# ATmega328P_Xplained_Mini_Target.net
KiCad netlist of a schematic drawn in Altium Designer
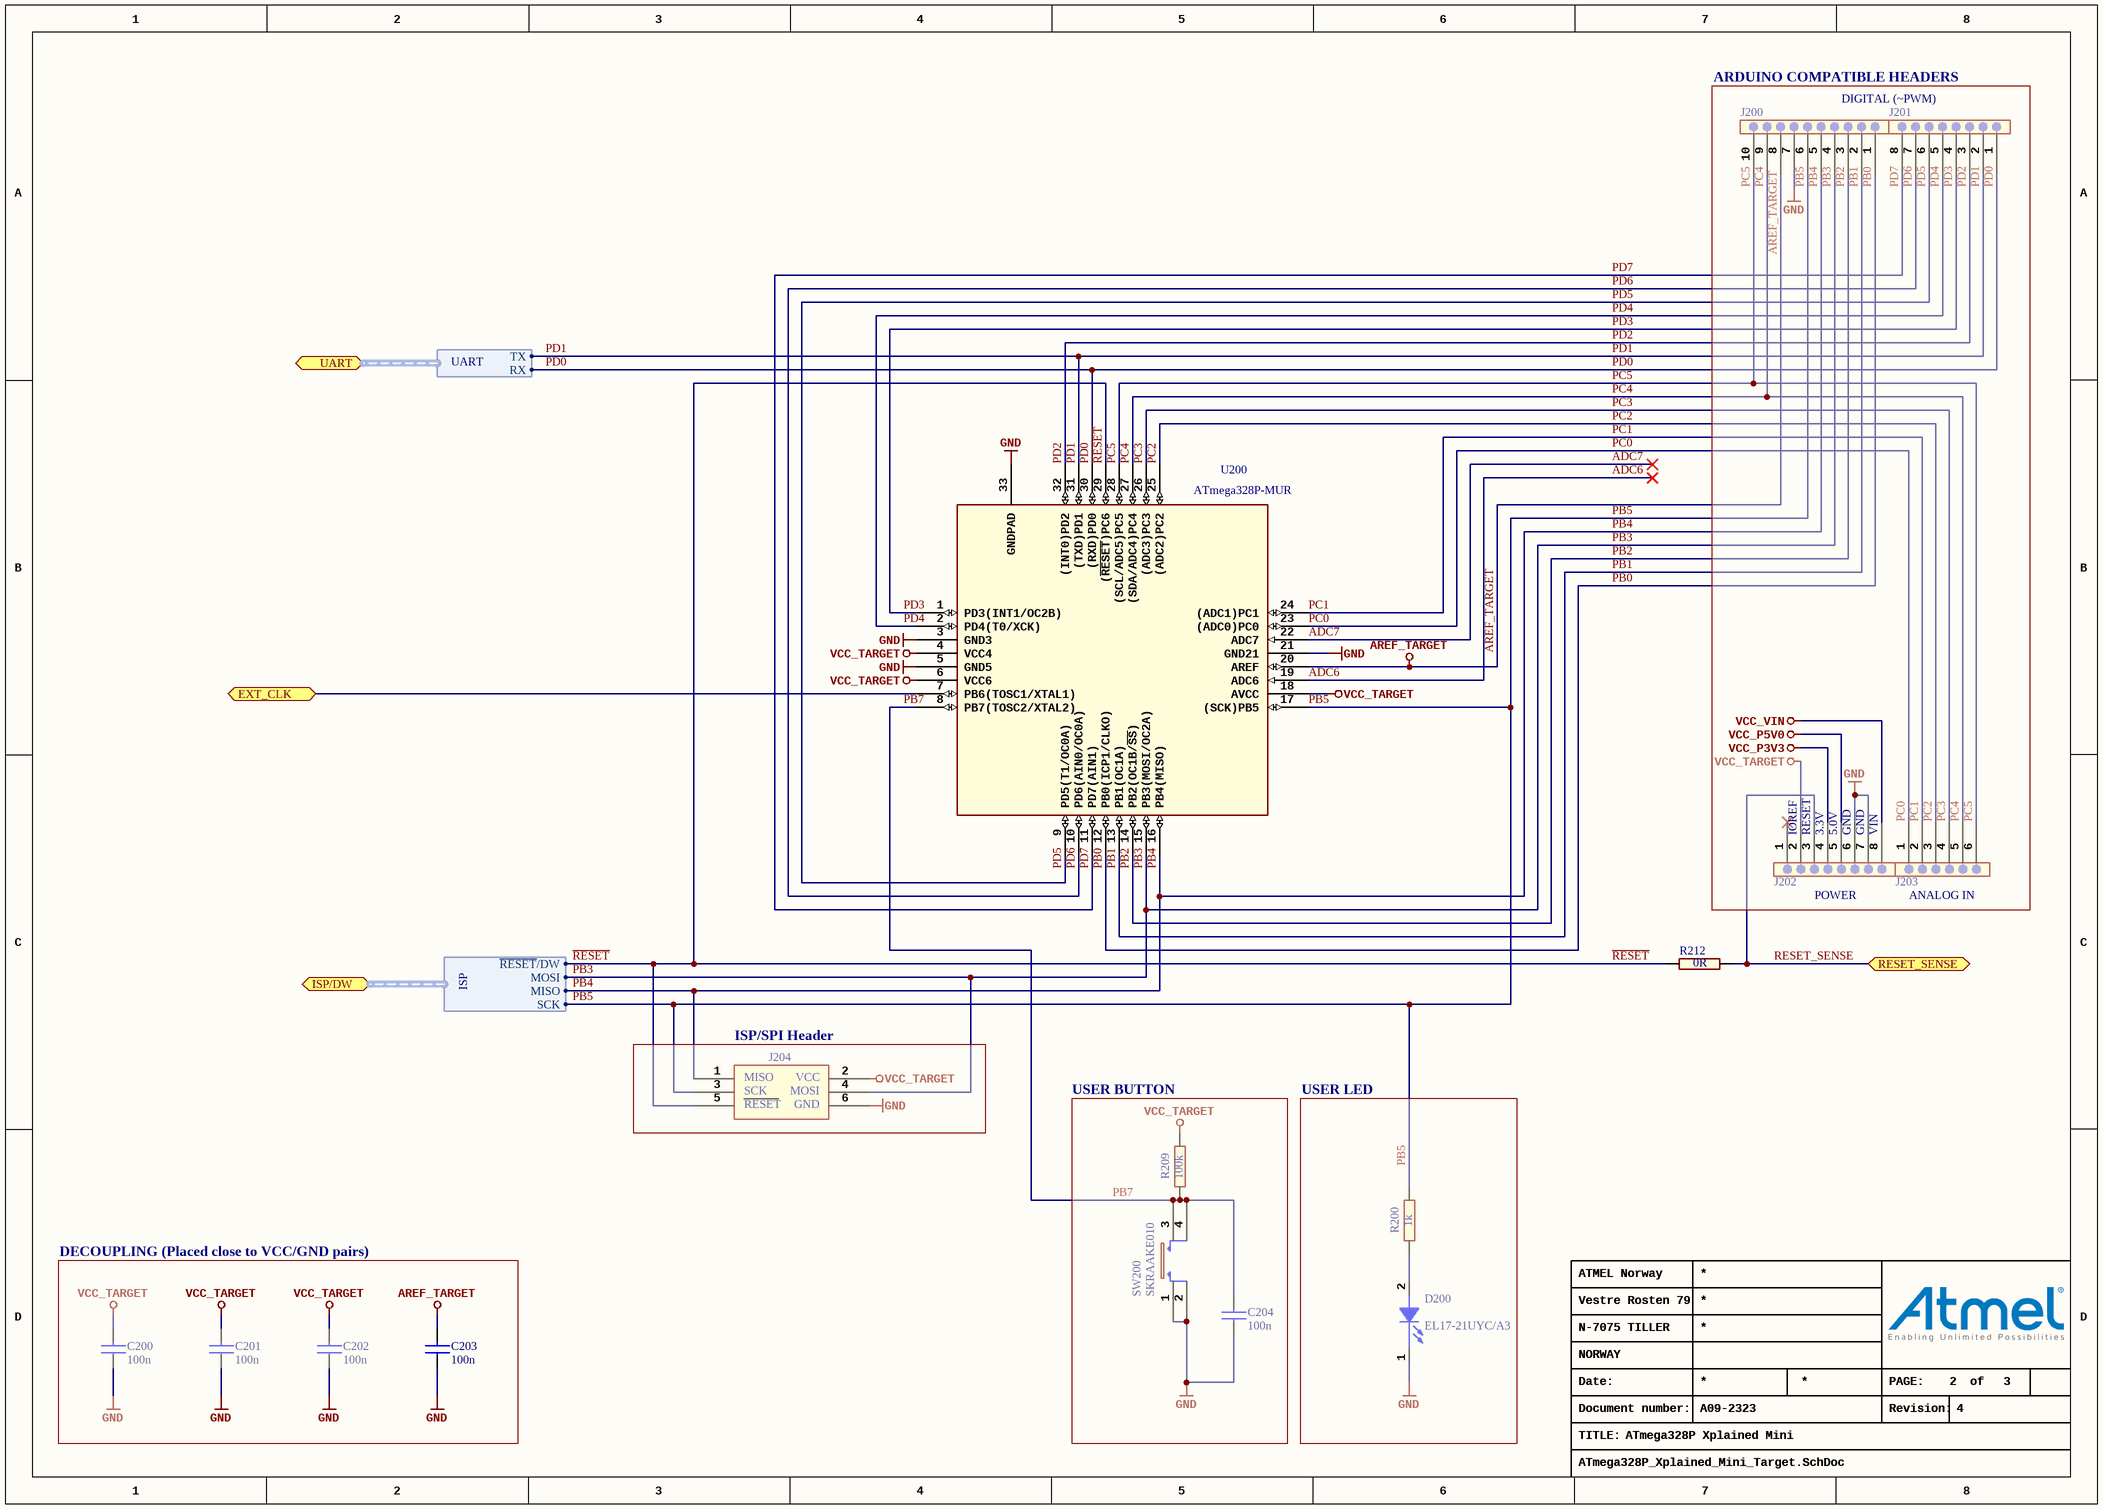
[diagram p0: ATmega328P_Xplained_Mini_Target.SchDoc]

(export (version "E")
  (design (tool "Eeschema 10.0.6"))
  (components
    (comp (ref "C200")
      (value "100n")
      (footprint "AP1-00001")
      (description "Ceramic capacitor, SMD 0402, X7R, 16V, +/-10%")
      (fields (field (name "TOLERANCE") "16V, +/-10%") (field (name "MANUFACTURER") "Kemet"))
      (libsource (lib "AltiumDbLib") (part "CAP-NONPOL"))
    )
    (comp (ref "C201")
      (value "100n")
      (footprint "AP1-00001")
      (description "Ceramic capacitor, SMD 0402, X7R, 16V, +/-10%")
      (fields (field (name "TOLERANCE") "16V, +/-10%") (field (name "MANUFACTURER") "Kemet"))
      (libsource (lib "AltiumDbLib") (part "CAP-NONPOL"))
    )
    (comp (ref "C202")
      (value "100n")
      (footprint "AP1-00001")
      (description "Ceramic capacitor, SMD 0402, X7R, 16V, +/-10%")
      (fields (field (name "TOLERANCE") "16V, +/-10%") (field (name "MANUFACTURER") "Kemet"))
      (libsource (lib "AltiumDbLib") (part "CAP-NONPOL"))
    )
    (comp (ref "C203")
      (value "100n")
      (footprint "AP1-00001")
      (description "Ceramic capacitor, SMD 0402, X7R, 16V, +/-10%")
      (fields (field (name "TOLERANCE") "16V, +/-10%") (field (name "MANUFACTURER") "Kemet"))
      (libsource (lib "AltiumDbLib") (part "CAP-NONPOL"))
    )
    (comp (ref "C204")
      (value "100n")
      (footprint "AP1-00001")
      (description "Ceramic capacitor, SMD 0402, X7R, 16V, +/-10%")
      (fields (field (name "TOLERANCE") "16V, +/-10%") (field (name "MANUFACTURER") "Kemet"))
      (libsource (lib "AltiumDbLib") (part "CAP-NONPOL"))
    )
    (comp (ref "D200")
      (value "EL17-21UYC/A3")
      (footprint "AP4-00013")
      (description "LED, Yellow, Wave length=591nm, SMD 0805, ±70°")
      (fields (field (name "MANUFACTURER") "Everlight") (field (name "MPN") "17-21UYC/S530-A3/TR8"))
      (libsource (lib "AltiumDbLib") (part "LED_12"))
    )
    (comp (ref "J200")
      (value "~")
      (footprint "AP8-00822")
      (description "1x10 receptacle pin header, low insertion force, 2.54mm pitch THM, Pin in Paste")
      (fields (field (name "MANUFACTURER") "SAMTEC") (field (name "MPN") "SSQ-110-21-F-S"))
      (libsource (lib "AltiumDbLib") (part "HEADER 1x10 FEMALE"))
    )
    (comp (ref "J201")
      (value "~")
      (footprint "AP8-00823")
      (description "1x8 receptacle pin header, low insertion force, 2.54mm pitch THM, Pin in Paste")
      (fields (field (name "MANUFACTURER") "SAMTEC") (field (name "MPN") "SSQ-108-21-F-S"))
      (libsource (lib "") (part "HEADER 1x8 FEMALE_1"))
    )
    (comp (ref "J202")
      (value "~")
      (footprint "AP8-00823")
      (description "1x8 receptacle pin header, low insertion force, 2.54mm pitch THM, Pin in Paste")
      (fields (field (name "MANUFACTURER") "SAMTEC") (field (name "MPN") "SSQ-108-21-F-S"))
      (libsource (lib "AltiumDbLib") (part "HEADER 1x8 FEMALE"))
    )
    (comp (ref "J203")
      (value "~")
      (footprint "AP8-00824")
      (description "1x6 receptacle pin header, low insertion force, 2.54mm pitch THM")
      (fields (field (name "MANUFACTURER") "SAMTEC") (field (name "MPN") "SSQ-106-21-F-S"))
      (libsource (lib "AltiumDbLib") (part "HEADER 1x6 FEMALE"))
    )
    (comp (ref "J204")
      (value "~")
      (footprint "AP8-00182")
      (description "2x3 pin header, 2.54 mm pitch, THM")
      (fields (field (name "MANUFACTURER") "SAMTEC") (field (name "MPN") "MTSW-103-08-L-D-276"))
      (libsource (lib "AltiumDbLib") (part "HEADER 2x3"))
    )
    (comp (ref "R200")
      (value "1k")
      (footprint "AP2-00000")
      (description "Thick film resistor, SMD 0402, 1/16W, 1%")
      (fields (field (name "TOLERANCE") "1 %") (field (name "MANUFACTURER") "ASJ"))
      (libsource (lib "AltiumDbLib") (part "R2"))
    )
    (comp (ref "R209")
      (value "100k")
      (footprint "AP2-00000")
      (description "Thick film resistor, SMD 0402, 1/16W, 1%")
      (fields (field (name "TOLERANCE") "1 %") (field (name "MANUFACTURER") "ASJ"))
      (libsource (lib "AltiumDbLib") (part "R2"))
    )
    (comp (ref "R212")
      (value "0R")
      (footprint "AP2-00000")
      (description "RES 0.0 OHM 1/16W 0402 SMD")
      (fields (field (name "TOLERANCE") "1 %") (field (name "MANUFACTURER") "(n/a)"))
      (libsource (lib "") (part "R2_1"))
    )
    (comp (ref "SW200")
      (value "SKRAAKE010")
      (footprint "AP8-00137")
      (description "6.2x6.2 mm SMD tact switch, same as A08-0091 but less force is needed")
      (fields (field (name "MANUFACTURER") "ALPS"))
      (libsource (lib "AltiumDbLib") (part "PUSHBUTTON1"))
    )
    (comp (ref "U200")
      (value "ATmega328P-MUR")
      (footprint "AP6-00155")
      (description "32k AVR with ADC/TWI/RS-232")
      (fields (field (name "MANUFACTURER") "ATMEL"))
      (libsource (lib "AltiumDbLib") (part "ATmega168-20MU"))
    )
  )
  (nets
    (net (code "3") (name "/ADC6") (class "Default")
      (node (ref "U200") (pin "19") (pinfunction "ADC6_19") (pintype "input+no_connect"))
    )
    (net (code "4") (name "/ADC7") (class "Default")
      (node (ref "U200") (pin "22") (pinfunction "ADC7_22") (pintype "input+no_connect"))
    )
    (net (code "5") (name "/EXT_CLK") (class "Default")
      (node (ref "U200") (pin "7") (pinfunction "PB6(TOSC1/XTAL1)_7") (pintype "bidirectional"))
    )
    (net (code "6") (name "/PB0") (class "Default")
      (node (ref "J200") (pin "1") (pinfunction "1_1") (pintype "passive"))
      (node (ref "U200") (pin "12") (pinfunction "PB0(ICP1/CLKO)_12") (pintype "bidirectional"))
    )
    (net (code "7") (name "/PB1") (class "Default")
      (node (ref "J200") (pin "2") (pinfunction "2_2") (pintype "passive"))
      (node (ref "U200") (pin "13") (pinfunction "PB1(OC1A)_13") (pintype "bidirectional"))
    )
    (net (code "8") (name "/PB2") (class "Default")
      (node (ref "J200") (pin "3") (pinfunction "3_3") (pintype "passive"))
      (node (ref "U200") (pin "14") (pinfunction "PB2(OC1B/~{SS})_14") (pintype "bidirectional"))
    )
    (net (code "9") (name "/PB3") (class "Default")
      (node (ref "J200") (pin "4") (pinfunction "4_4") (pintype "passive"))
      (node (ref "J204") (pin "4") (pinfunction "4_4") (pintype "passive"))
      (node (ref "U200") (pin "15") (pinfunction "PB3(MOSI/OC2A)_15") (pintype "bidirectional"))
    )
    (net (code "10") (name "/PB4") (class "Default")
      (node (ref "J200") (pin "5") (pinfunction "5_5") (pintype "passive"))
      (node (ref "J204") (pin "1") (pinfunction "1_1") (pintype "passive"))
      (node (ref "U200") (pin "16") (pinfunction "PB4(MISO)_16") (pintype "bidirectional"))
    )
    (net (code "11") (name "/PB5") (class "Default")
      (node (ref "J200") (pin "6") (pinfunction "6_6") (pintype "passive"))
      (node (ref "J204") (pin "3") (pinfunction "3_3") (pintype "passive"))
      (node (ref "R200") (pin "2") (pinfunction "2_2") (pintype "passive"))
      (node (ref "U200") (pin "17") (pinfunction "(SCK)PB5_17") (pintype "bidirectional"))
    )
    (net (code "12") (name "/PB7") (class "Default")
      (node (ref "C204") (pin "2") (pinfunction "2_2") (pintype "passive"))
      (node (ref "R209") (pin "1") (pinfunction "1_1") (pintype "passive"))
      (node (ref "SW200") (pin "3") (pinfunction "3_3") (pintype "passive"))
      (node (ref "SW200") (pin "4") (pinfunction "4_4") (pintype "passive"))
      (node (ref "U200") (pin "8") (pinfunction "PB7(TOSC2/XTAL2)_8") (pintype "bidirectional"))
    )
    (net (code "13") (name "/PC0") (class "Default")
      (node (ref "J203") (pin "1") (pinfunction "1_1") (pintype "passive"))
      (node (ref "U200") (pin "23") (pinfunction "(ADC0)PC0_23") (pintype "bidirectional"))
    )
    (net (code "14") (name "/PC1") (class "Default")
      (node (ref "J203") (pin "2") (pinfunction "2_2") (pintype "passive"))
      (node (ref "U200") (pin "24") (pinfunction "(ADC1)PC1_24") (pintype "bidirectional"))
    )
    (net (code "15") (name "/PC2") (class "Default")
      (node (ref "J203") (pin "3") (pinfunction "3_3") (pintype "passive"))
      (node (ref "U200") (pin "25") (pinfunction "(ADC2)PC2_25") (pintype "bidirectional"))
    )
    (net (code "16") (name "/PC3") (class "Default")
      (node (ref "J203") (pin "4") (pinfunction "4_4") (pintype "passive"))
      (node (ref "U200") (pin "26") (pinfunction "(ADC3)PC3_26") (pintype "bidirectional"))
    )
    (net (code "17") (name "/PC4") (class "Default")
      (node (ref "J200") (pin "9") (pinfunction "9_9") (pintype "passive"))
      (node (ref "J203") (pin "5") (pinfunction "5_5") (pintype "passive"))
      (node (ref "U200") (pin "27") (pinfunction "(SDA/ADC4)PC4_27") (pintype "bidirectional"))
    )
    (net (code "18") (name "/PC5") (class "Default")
      (node (ref "J200") (pin "10") (pinfunction "10_10") (pintype "passive"))
      (node (ref "J203") (pin "6") (pinfunction "6_6") (pintype "passive"))
      (node (ref "U200") (pin "28") (pinfunction "(SCL/ADC5)PC5_28") (pintype "bidirectional"))
    )
    (net (code "19") (name "/PD0") (class "Default")
      (node (ref "J201") (pin "1") (pinfunction "1_1") (pintype "passive"))
      (node (ref "U200") (pin "30") (pinfunction "(RXD)PD0_30") (pintype "bidirectional"))
    )
    (net (code "20") (name "/PD1") (class "Default")
      (node (ref "J201") (pin "2") (pinfunction "2_2") (pintype "passive"))
      (node (ref "U200") (pin "31") (pinfunction "(TXD)PD1_31") (pintype "bidirectional"))
    )
    (net (code "21") (name "/PD2") (class "Default")
      (node (ref "J201") (pin "3") (pinfunction "3_3") (pintype "passive"))
      (node (ref "U200") (pin "32") (pinfunction "(INT0)PD2_32") (pintype "bidirectional"))
    )
    (net (code "22") (name "/PD3") (class "Default")
      (node (ref "J201") (pin "4") (pinfunction "4_4") (pintype "passive"))
      (node (ref "U200") (pin "1") (pinfunction "PD3(INT1/OC2B)_1") (pintype "bidirectional"))
    )
    (net (code "23") (name "/PD4") (class "Default")
      (node (ref "J201") (pin "5") (pinfunction "5_5") (pintype "passive"))
      (node (ref "U200") (pin "2") (pinfunction "PD4(T0/XCK)_2") (pintype "bidirectional"))
    )
    (net (code "24") (name "/PD5") (class "Default")
      (node (ref "J201") (pin "6") (pinfunction "6_6") (pintype "passive"))
      (node (ref "U200") (pin "9") (pinfunction "PD5(T1/OC0A)_9") (pintype "bidirectional"))
    )
    (net (code "25") (name "/PD6") (class "Default")
      (node (ref "J201") (pin "7") (pinfunction "7_7") (pintype "passive"))
      (node (ref "U200") (pin "10") (pinfunction "PD6(AIN0/OC0A)_10") (pintype "bidirectional"))
    )
    (net (code "26") (name "/PD7") (class "Default")
      (node (ref "J201") (pin "8") (pinfunction "8_8") (pintype "passive"))
      (node (ref "U200") (pin "11") (pinfunction "PD7(AIN1)_11") (pintype "bidirectional"))
    )
    (net (code "27") (name "/RESET_SENSE") (class "Default")
      (node (ref "J202") (pin "3") (pinfunction "3_3") (pintype "passive"))
      (node (ref "R212") (pin "2") (pinfunction "2_2") (pintype "passive"))
    )
    (net (code "30") (name "/~{RESET}") (class "Default")
      (node (ref "J204") (pin "5") (pinfunction "5_5") (pintype "passive"))
      (node (ref "R212") (pin "1") (pinfunction "1_1") (pintype "passive"))
      (node (ref "U200") (pin "29") (pinfunction "(~{RESET})PC6_29") (pintype "bidirectional"))
    )
    (net (code "31") (name "AREF_TARGET") (class "Default")
      (node (ref "C203") (pin "2") (pinfunction "2_2") (pintype "passive"))
      (node (ref "J200") (pin "8") (pinfunction "8_8") (pintype "passive"))
      (node (ref "U200") (pin "20") (pinfunction "AREF_20") (pintype "bidirectional"))
    )
    (net (code "32") (name "GND") (class "Default")
      (node (ref "C200") (pin "1") (pinfunction "1_1") (pintype "passive"))
      (node (ref "C201") (pin "1") (pinfunction "1_1") (pintype "passive"))
      (node (ref "C202") (pin "1") (pinfunction "1_1") (pintype "passive"))
      (node (ref "C203") (pin "1") (pinfunction "1_1") (pintype "passive"))
      (node (ref "C204") (pin "1") (pinfunction "1_1") (pintype "passive"))
      (node (ref "D200") (pin "1") (pinfunction "CATHODE_1") (pintype "passive"))
      (node (ref "J200") (pin "7") (pinfunction "7_7") (pintype "passive"))
      (node (ref "J202") (pin "6") (pinfunction "6_6") (pintype "passive"))
      (node (ref "J202") (pin "7") (pinfunction "7_7") (pintype "passive"))
      (node (ref "J204") (pin "6") (pinfunction "6_6") (pintype "passive"))
      (node (ref "SW200") (pin "1") (pinfunction "1_1") (pintype "passive"))
      (node (ref "SW200") (pin "2") (pinfunction "2_2") (pintype "passive"))
      (node (ref "U200") (pin "21") (pinfunction "GND21_21") (pintype "power_in"))
      (node (ref "U200") (pin "3") (pinfunction "GND3_3") (pintype "power_in"))
      (node (ref "U200") (pin "33") (pinfunction "GNDPAD_33") (pintype "passive"))
      (node (ref "U200") (pin "5") (pinfunction "GND5_5") (pintype "power_in"))
    )
    (net (code "33") (name "Net-(D200-ANODE)") (class "Default")
      (node (ref "D200") (pin "2") (pinfunction "ANODE_2") (pintype "passive"))
      (node (ref "R200") (pin "1") (pinfunction "1_1") (pintype "passive"))
    )
    (net (code "34") (name "VCC_P3V3") (class "Default")
      (node (ref "J202") (pin "4") (pinfunction "4_4") (pintype "passive"))
    )
    (net (code "35") (name "VCC_P5V0") (class "Default")
      (node (ref "J202") (pin "5") (pinfunction "5_5") (pintype "passive"))
    )
    (net (code "36") (name "VCC_TARGET") (class "Default")
      (node (ref "C200") (pin "2") (pinfunction "2_2") (pintype "passive"))
      (node (ref "C201") (pin "2") (pinfunction "2_2") (pintype "passive"))
      (node (ref "C202") (pin "2") (pinfunction "2_2") (pintype "passive"))
      (node (ref "J202") (pin "2") (pinfunction "2_2") (pintype "passive"))
      (node (ref "J204") (pin "2") (pinfunction "2_2") (pintype "passive"))
      (node (ref "R209") (pin "2") (pinfunction "2_2") (pintype "passive"))
      (node (ref "U200") (pin "18") (pinfunction "AVCC_18") (pintype "power_in"))
      (node (ref "U200") (pin "4") (pinfunction "VCC4_4") (pintype "power_in"))
      (node (ref "U200") (pin "6") (pinfunction "VCC6_6") (pintype "power_in"))
    )
    (net (code "37") (name "VCC_VIN") (class "Default")
      (node (ref "J202") (pin "8") (pinfunction "8_8") (pintype "passive"))
    )
    (net (code "38") (name "unconnected-(J202-Pad1)") (class "Default")
      (node (ref "J202") (pin "1") (pinfunction "1_1") (pintype "passive+no_connect"))
    )
  )
)
